# GeniusTop.net
KiCad netlist of a schematic drawn in EAGLE
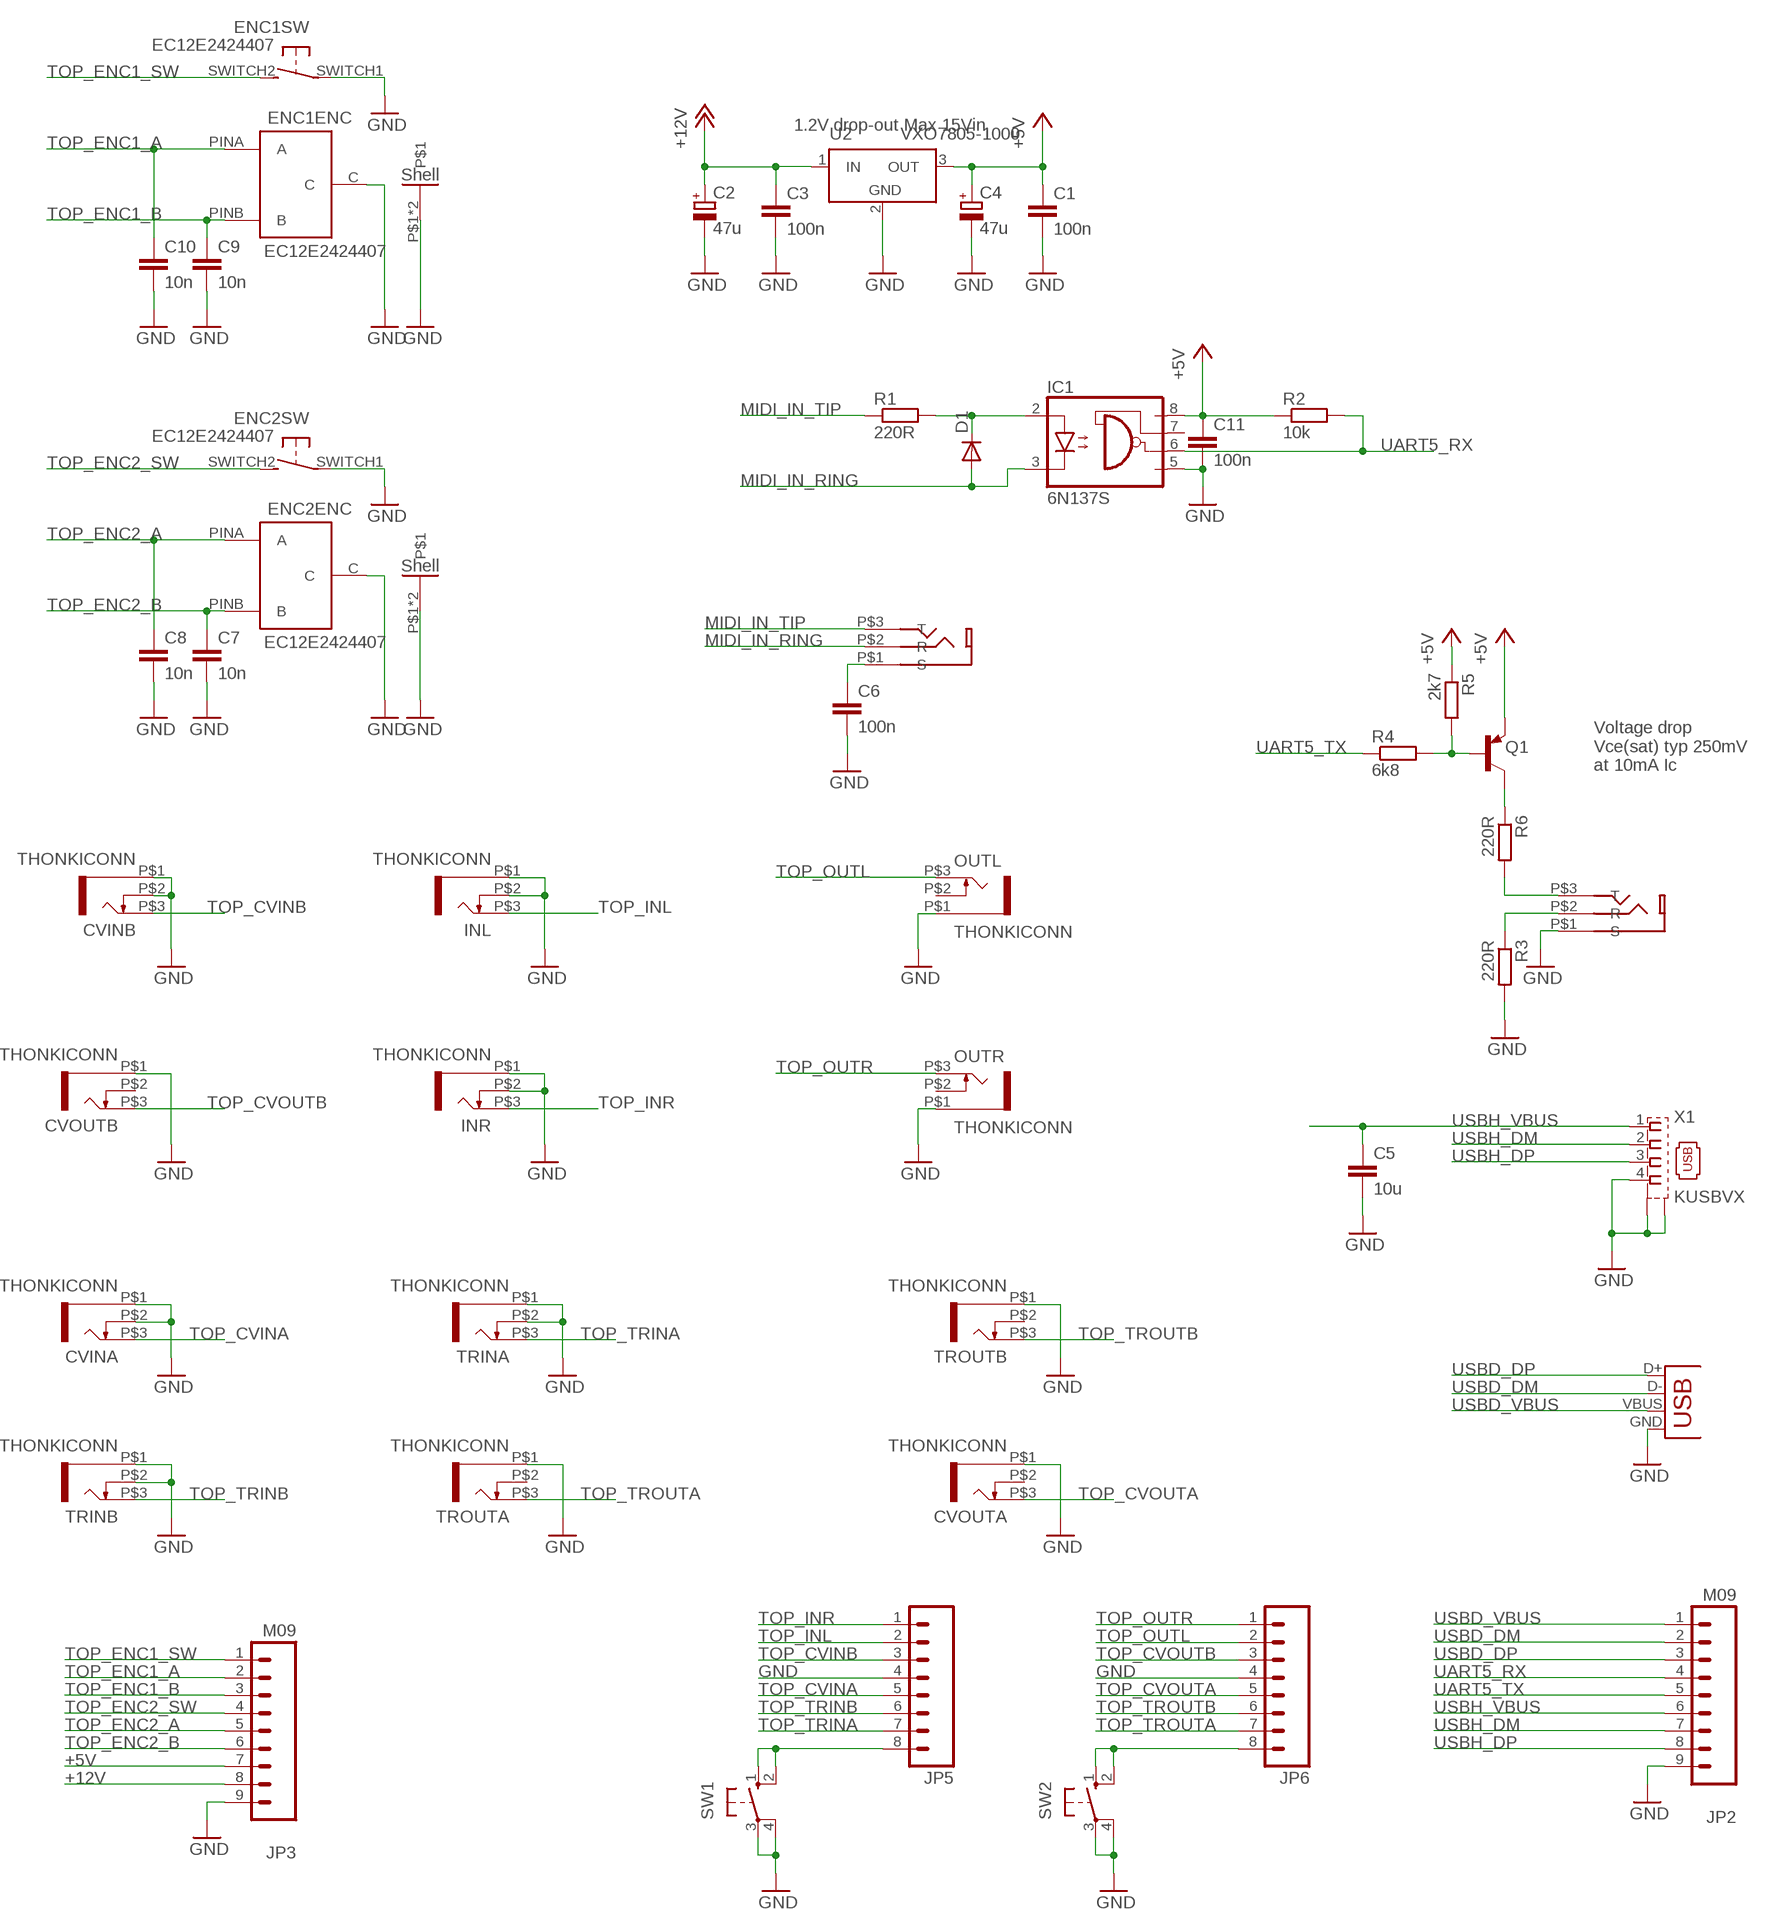
[diagram p0: schematic, sheet 1]

(export (version "E")
  (design (tool "Eeschema 10.0.6"))
  (components
    (comp (ref "C1")
      (value "100n")
      (footprint "eagle-import:C0603")
      (libsource (lib "eagle-import") (part "C-EUC0603"))
    )
    (comp (ref "C2")
      (value "47u")
      (footprint "eagle-import:CPOL-5")
      (libsource (lib "eagle-import") (part "CPOL-EU153CLV-0505"))
    )
    (comp (ref "C3")
      (value "100n")
      (footprint "eagle-import:C0603")
      (libsource (lib "eagle-import") (part "C-EUC0603"))
    )
    (comp (ref "C4")
      (value "47u")
      (footprint "eagle-import:CPOL-5")
      (libsource (lib "eagle-import") (part "CPOL-EU153CLV-0505"))
    )
    (comp (ref "C5")
      (value "10u")
      (footprint "eagle-import:C1206")
      (libsource (lib "eagle-import") (part "C-EUC1206"))
    )
    (comp (ref "C6")
      (value "100n")
      (footprint "eagle-import:C0603")
      (libsource (lib "eagle-import") (part "C-EUC0603"))
    )
    (comp (ref "C7")
      (value "10n")
      (footprint "eagle-import:C0603")
      (libsource (lib "eagle-import") (part "C-EUC0603"))
    )
    (comp (ref "C8")
      (value "10n")
      (footprint "eagle-import:C0603")
      (libsource (lib "eagle-import") (part "C-EUC0603"))
    )
    (comp (ref "C9")
      (value "10n")
      (footprint "eagle-import:C0603")
      (libsource (lib "eagle-import") (part "C-EUC0603"))
    )
    (comp (ref "C10")
      (value "10n")
      (footprint "eagle-import:C0603")
      (libsource (lib "eagle-import") (part "C-EUC0603"))
    )
    (comp (ref "C11")
      (value "100n")
      (footprint "eagle-import:C0603")
      (libsource (lib "eagle-import") (part "C-EUC0603"))
    )
    (comp (ref "CVINA")
      (value "THONKICONN")
      (footprint "eagle-import:THONKICONN")
      (libsource (lib "eagle-import") (part "THONKICONN"))
    )
    (comp (ref "CVINB")
      (value "THONKICONN")
      (footprint "eagle-import:THONKICONN")
      (libsource (lib "eagle-import") (part "THONKICONN"))
    )
    (comp (ref "CVOUTA")
      (value "THONKICONN")
      (footprint "eagle-import:THONKICONN")
      (libsource (lib "eagle-import") (part "THONKICONN"))
    )
    (comp (ref "CVOUTB")
      (value "THONKICONN")
      (footprint "eagle-import:THONKICONN")
      (libsource (lib "eagle-import") (part "THONKICONN"))
    )
    (comp (ref "D1")
      (value "DIODESOD-123")
      (footprint "eagle-import:SOD-123")
      (libsource (lib "eagle-import") (part "DIODESOD-123"))
    )
    (comp (ref "ENC1")
      (value "EC12E2424407")
      (footprint "eagle-import:EC12E2424407")
      (libsource (lib "eagle-import") (part "EC12E2424407"))
    )
    (comp (ref "ENC2")
      (value "EC12E2424407")
      (footprint "eagle-import:EC12E2424407")
      (libsource (lib "eagle-import") (part "EC12E2424407"))
    )
    (comp (ref "IC1")
      (value "6N137S")
      (footprint "eagle-import:DIL8-SMD")
      (libsource (lib "eagle-import") (part "6N137S"))
    )
    (comp (ref "INL")
      (value "THONKICONN")
      (footprint "eagle-import:THONKICONN")
      (libsource (lib "eagle-import") (part "THONKICONN"))
    )
    (comp (ref "INR")
      (value "THONKICONN")
      (footprint "eagle-import:THONKICONN")
      (libsource (lib "eagle-import") (part "THONKICONN"))
    )
    (comp (ref "JP2")
      (value "M09")
      (footprint "eagle-import:1X09")
      (libsource (lib "eagle-import") (part "M09"))
    )
    (comp (ref "JP3")
      (value "M09")
      (footprint "eagle-import:1X09")
      (libsource (lib "eagle-import") (part "M09"))
    )
    (comp (ref "JP5")
      (value "M081X08")
      (footprint "eagle-import:1X08")
      (libsource (lib "eagle-import") (part "M081X08"))
    )
    (comp (ref "JP6")
      (value "M081X08")
      (footprint "eagle-import:1X08")
      (libsource (lib "eagle-import") (part "M081X08"))
    )
    (comp (ref "MIDI_IN")
      (value "THONKICONN_STEREO")
      (footprint "eagle-import:THONKICONN_STEREO")
      (libsource (lib "eagle-import") (part "THONKICONN_STEREO"))
    )
    (comp (ref "MIDI_OUT")
      (value "THONKICONN_STEREO")
      (footprint "eagle-import:THONKICONN_STEREO")
      (libsource (lib "eagle-import") (part "THONKICONN_STEREO"))
    )
    (comp (ref "OUTL")
      (value "THONKICONN")
      (footprint "eagle-import:THONKICONN")
      (libsource (lib "eagle-import") (part "THONKICONN"))
    )
    (comp (ref "OUTR")
      (value "THONKICONN")
      (footprint "eagle-import:THONKICONN")
      (libsource (lib "eagle-import") (part "THONKICONN"))
    )
    (comp (ref "Q1")
      (value "MMBT3906LT1-PNP-SOT23-BEC")
      (footprint "eagle-import:SOT23-BEC")
      (libsource (lib "eagle-import") (part "-PNP-SOT23-BECMMBT3906LT1"))
    )
    (comp (ref "R1")
      (value "220R")
      (footprint "eagle-import:0603")
      (libsource (lib "eagle-import") (part "R-EU_R0603"))
    )
    (comp (ref "R2")
      (value "10k")
      (footprint "eagle-import:0603")
      (libsource (lib "eagle-import") (part "R-EU_R0603"))
    )
    (comp (ref "R3")
      (value "220R")
      (footprint "eagle-import:0603")
      (libsource (lib "eagle-import") (part "R-EU_R0603"))
    )
    (comp (ref "R4")
      (value "6k8")
      (footprint "eagle-import:0603")
      (libsource (lib "eagle-import") (part "R-EU_R0603"))
    )
    (comp (ref "R5")
      (value "2k7")
      (footprint "eagle-import:0603")
      (libsource (lib "eagle-import") (part "R-EU_R0603"))
    )
    (comp (ref "R6")
      (value "220R")
      (footprint "eagle-import:0603")
      (libsource (lib "eagle-import") (part "R-EU_R0603"))
    )
    (comp (ref "SW1")
      (value "10-XX")
      (footprint "eagle-import:B3F-10XX")
      (fields (field (name "MPN") "B3F-1000"))
      (libsource (lib "eagle-import") (part "10-XX"))
    )
    (comp (ref "SW2")
      (value "10-XX")
      (footprint "eagle-import:B3F-10XX")
      (fields (field (name "MPN") "B3F-1000"))
      (libsource (lib "eagle-import") (part "10-XX"))
    )
    (comp (ref "TRINA")
      (value "THONKICONN")
      (footprint "eagle-import:THONKICONN")
      (libsource (lib "eagle-import") (part "THONKICONN"))
    )
    (comp (ref "TRINB")
      (value "THONKICONN")
      (footprint "eagle-import:THONKICONN")
      (libsource (lib "eagle-import") (part "THONKICONN"))
    )
    (comp (ref "TROUTA")
      (value "THONKICONN")
      (footprint "eagle-import:THONKICONN")
      (libsource (lib "eagle-import") (part "THONKICONN"))
    )
    (comp (ref "TROUTB")
      (value "THONKICONN")
      (footprint "eagle-import:THONKICONN")
      (libsource (lib "eagle-import") (part "THONKICONN"))
    )
    (comp (ref "U2")
      (value "VXO7805-1000")
      (footprint "eagle-import:TSR-1-2450")
      (libsource (lib "eagle-import") (part "TSR-1-2450"))
    )
    (comp (ref "X1")
      (value "KUSBVX")
      (footprint "eagle-import:KUSBVX")
      (libsource (lib "eagle-import") (part "KUSBVX"))
    )
    (comp (ref "X2")
      (value "USBPTH-VERTICAL")
      (footprint "eagle-import:USB-B-PTH-VERTICAL")
      (libsource (lib "eagle-import") (part "USBPTH-VERTICAL"))
    )
  )
  (nets
    (net (code "1") (name "+5V") (class "Default")
      (node (ref "C1") (pin "1") (pinfunction "1_1") (pintype "passive"))
      (node (ref "C11") (pin "1") (pinfunction "1_1") (pintype "passive"))
      (node (ref "C4") (pin "+") (pinfunction "+_+") (pintype "passive"))
      (node (ref "IC1") (pin "8") (pinfunction "VCC_8") (pintype "passive"))
      (node (ref "JP3") (pin "7") (pinfunction "7_7") (pintype "passive"))
      (node (ref "Q1") (pin "E") (pinfunction "E_E") (pintype "passive"))
      (node (ref "R2") (pin "1") (pinfunction "1_1") (pintype "passive"))
      (node (ref "R5") (pin "1") (pinfunction "1_1") (pintype "passive"))
      (node (ref "U2") (pin "3") (pinfunction "OUT_3") (pintype "output"))
    )
    (net (code "2") (name "+12V") (class "Default")
      (node (ref "C2") (pin "+") (pinfunction "+_+") (pintype "passive"))
      (node (ref "C3") (pin "1") (pinfunction "1_1") (pintype "passive"))
      (node (ref "JP3") (pin "8") (pinfunction "8_8") (pintype "passive"))
      (node (ref "U2") (pin "1") (pinfunction "IN_1") (pintype "input"))
    )
    (net (code "3") (name "/MIDI_IN_RING") (class "Default")
      (node (ref "D1") (pin "A") (pinfunction "A_A") (pintype "passive"))
      (node (ref "IC1") (pin "3") (pinfunction "C_3") (pintype "passive"))
      (node (ref "MIDI_IN") (pin "P$2") (pinfunction "R_P$2") (pintype "bidirectional"))
    )
    (net (code "4") (name "/MIDI_IN_TIP") (class "Default")
      (node (ref "MIDI_IN") (pin "P$3") (pinfunction "T_P$3") (pintype "bidirectional"))
      (node (ref "R1") (pin "1") (pinfunction "1_1") (pintype "passive"))
    )
    (net (code "5") (name "/TOP_CVINA") (class "Default")
      (node (ref "CVINA") (pin "P$3") (pinfunction "3_P$3") (pintype "passive"))
      (node (ref "JP5") (pin "5") (pinfunction "5_5") (pintype "passive"))
    )
    (net (code "6") (name "/TOP_CVINB") (class "Default")
      (node (ref "CVINB") (pin "P$3") (pinfunction "3_P$3") (pintype "passive"))
      (node (ref "JP5") (pin "3") (pinfunction "3_3") (pintype "passive"))
    )
    (net (code "7") (name "/TOP_CVOUTA") (class "Default")
      (node (ref "CVOUTA") (pin "P$3") (pinfunction "3_P$3") (pintype "passive"))
      (node (ref "JP6") (pin "5") (pinfunction "5_5") (pintype "passive"))
    )
    (net (code "8") (name "/TOP_CVOUTB") (class "Default")
      (node (ref "CVOUTB") (pin "P$3") (pinfunction "3_P$3") (pintype "passive"))
      (node (ref "JP6") (pin "3") (pinfunction "3_3") (pintype "passive"))
    )
    (net (code "9") (name "/TOP_ENC1_A") (class "Default")
      (node (ref "C10") (pin "1") (pinfunction "1_1") (pintype "passive"))
      (node (ref "ENC1") (pin "PINA") (pinfunction "A_PINA") (pintype "bidirectional"))
      (node (ref "JP3") (pin "2") (pinfunction "2_2") (pintype "passive"))
    )
    (net (code "10") (name "/TOP_ENC1_B") (class "Default")
      (node (ref "C9") (pin "1") (pinfunction "1_1") (pintype "passive"))
      (node (ref "ENC1") (pin "PINB") (pinfunction "B_PINB") (pintype "bidirectional"))
      (node (ref "JP3") (pin "3") (pinfunction "3_3") (pintype "passive"))
    )
    (net (code "11") (name "/TOP_ENC1_SW") (class "Default")
      (node (ref "ENC1") (pin "SWITCH2") (pinfunction "S_SWITCH2") (pintype "passive"))
      (node (ref "JP3") (pin "1") (pinfunction "1_1") (pintype "passive"))
    )
    (net (code "12") (name "/TOP_ENC2_A") (class "Default")
      (node (ref "C8") (pin "1") (pinfunction "1_1") (pintype "passive"))
      (node (ref "ENC2") (pin "PINA") (pinfunction "A_PINA") (pintype "bidirectional"))
      (node (ref "JP3") (pin "5") (pinfunction "5_5") (pintype "passive"))
    )
    (net (code "13") (name "/TOP_ENC2_B") (class "Default")
      (node (ref "C7") (pin "1") (pinfunction "1_1") (pintype "passive"))
      (node (ref "ENC2") (pin "PINB") (pinfunction "B_PINB") (pintype "bidirectional"))
      (node (ref "JP3") (pin "6") (pinfunction "6_6") (pintype "passive"))
    )
    (net (code "14") (name "/TOP_ENC2_SW") (class "Default")
      (node (ref "ENC2") (pin "SWITCH2") (pinfunction "S_SWITCH2") (pintype "passive"))
      (node (ref "JP3") (pin "4") (pinfunction "4_4") (pintype "passive"))
    )
    (net (code "15") (name "/TOP_INL") (class "Default")
      (node (ref "INL") (pin "P$3") (pinfunction "3_P$3") (pintype "passive"))
      (node (ref "JP5") (pin "2") (pinfunction "2_2") (pintype "passive"))
    )
    (net (code "16") (name "/TOP_INR") (class "Default")
      (node (ref "INR") (pin "P$3") (pinfunction "3_P$3") (pintype "passive"))
      (node (ref "JP5") (pin "1") (pinfunction "1_1") (pintype "passive"))
    )
    (net (code "17") (name "/TOP_OUTL") (class "Default")
      (node (ref "JP6") (pin "2") (pinfunction "2_2") (pintype "passive"))
      (node (ref "OUTL") (pin "P$3") (pinfunction "3_P$3") (pintype "passive"))
    )
    (net (code "18") (name "/TOP_OUTR") (class "Default")
      (node (ref "JP6") (pin "1") (pinfunction "1_1") (pintype "passive"))
      (node (ref "OUTR") (pin "P$3") (pinfunction "3_P$3") (pintype "passive"))
    )
    (net (code "19") (name "/TOP_TRINA") (class "Default")
      (node (ref "JP5") (pin "7") (pinfunction "7_7") (pintype "passive"))
      (node (ref "TRINA") (pin "P$3") (pinfunction "3_P$3") (pintype "passive"))
    )
    (net (code "20") (name "/TOP_TRINB") (class "Default")
      (node (ref "JP5") (pin "6") (pinfunction "6_6") (pintype "passive"))
      (node (ref "TRINB") (pin "P$3") (pinfunction "3_P$3") (pintype "passive"))
    )
    (net (code "21") (name "/TOP_TROUTA") (class "Default")
      (node (ref "JP6") (pin "7") (pinfunction "7_7") (pintype "passive"))
      (node (ref "TROUTA") (pin "P$3") (pinfunction "3_P$3") (pintype "passive"))
    )
    (net (code "22") (name "/TOP_TROUTB") (class "Default")
      (node (ref "JP6") (pin "6") (pinfunction "6_6") (pintype "passive"))
      (node (ref "TROUTB") (pin "P$3") (pinfunction "3_P$3") (pintype "passive"))
    )
    (net (code "23") (name "/UART5_RX") (class "Default")
      (node (ref "IC1") (pin "6") (pinfunction "VO_6") (pintype "passive"))
      (node (ref "JP2") (pin "4") (pinfunction "4_4") (pintype "passive"))
      (node (ref "R2") (pin "2") (pinfunction "2_2") (pintype "passive"))
    )
    (net (code "24") (name "/UART5_TX") (class "Default")
      (node (ref "JP2") (pin "5") (pinfunction "5_5") (pintype "passive"))
      (node (ref "R4") (pin "1") (pinfunction "1_1") (pintype "passive"))
    )
    (net (code "25") (name "/USBD_DM") (class "Default")
      (node (ref "JP2") (pin "2") (pinfunction "2_2") (pintype "passive"))
      (node (ref "X2") (pin "D-") (pinfunction "D-_D-") (pintype "bidirectional"))
    )
    (net (code "26") (name "/USBD_DP") (class "Default")
      (node (ref "JP2") (pin "3") (pinfunction "3_3") (pintype "passive"))
      (node (ref "X2") (pin "D+") (pinfunction "D+_D+") (pintype "bidirectional"))
    )
    (net (code "27") (name "/USBD_VBUS") (class "Default")
      (node (ref "JP2") (pin "1") (pinfunction "1_1") (pintype "passive"))
      (node (ref "X2") (pin "VBUS") (pinfunction "VBUS_VBUS") (pintype "bidirectional"))
    )
    (net (code "28") (name "/USBH_DM") (class "Default")
      (node (ref "JP2") (pin "7") (pinfunction "7_7") (pintype "passive"))
      (node (ref "X1") (pin "2") (pinfunction "2_2") (pintype "passive"))
    )
    (net (code "29") (name "/USBH_DP") (class "Default")
      (node (ref "JP2") (pin "8") (pinfunction "8_8") (pintype "passive"))
      (node (ref "X1") (pin "3") (pinfunction "3_3") (pintype "passive"))
    )
    (net (code "30") (name "/USBH_VBUS") (class "Default")
      (node (ref "C5") (pin "1") (pinfunction "1_1") (pintype "passive"))
      (node (ref "JP2") (pin "6") (pinfunction "6_6") (pintype "passive"))
      (node (ref "X1") (pin "1") (pinfunction "1_1") (pintype "passive"))
    )
    (net (code "31") (name "GND") (class "Default")
      (node (ref "C1") (pin "2") (pinfunction "2_2") (pintype "passive"))
      (node (ref "C10") (pin "2") (pinfunction "2_2") (pintype "passive"))
      (node (ref "C11") (pin "2") (pinfunction "2_2") (pintype "passive"))
      (node (ref "C2") (pin "-") (pinfunction "-_-") (pintype "passive"))
      (node (ref "C3") (pin "2") (pinfunction "2_2") (pintype "passive"))
      (node (ref "C4") (pin "-") (pinfunction "-_-") (pintype "passive"))
      (node (ref "C5") (pin "2") (pinfunction "2_2") (pintype "passive"))
      (node (ref "C6") (pin "2") (pinfunction "2_2") (pintype "passive"))
      (node (ref "C7") (pin "2") (pinfunction "2_2") (pintype "passive"))
      (node (ref "C8") (pin "2") (pinfunction "2_2") (pintype "passive"))
      (node (ref "C9") (pin "2") (pinfunction "2_2") (pintype "passive"))
      (node (ref "CVINA") (pin "P$1") (pinfunction "5_P$1") (pintype "passive"))
      (node (ref "CVINA") (pin "P$2") (pinfunction "4_P$2") (pintype "passive"))
      (node (ref "CVINB") (pin "P$1") (pinfunction "5_P$1") (pintype "passive"))
      (node (ref "CVINB") (pin "P$2") (pinfunction "4_P$2") (pintype "passive"))
      (node (ref "CVOUTA") (pin "P$1") (pinfunction "5_P$1") (pintype "passive"))
      (node (ref "CVOUTB") (pin "P$1") (pinfunction "5_P$1") (pintype "passive"))
      (node (ref "ENC1") (pin "C") (pinfunction "C_C") (pintype "bidirectional"))
      (node (ref "ENC1") (pin "P$1") (pinfunction "P$1_P$1") (pintype "bidirectional"))
      (node (ref "ENC1") (pin "P$2") (pinfunction "P$1_P$2") (pintype "bidirectional"))
      (node (ref "ENC1") (pin "SWITCH1") (pinfunction "P_SWITCH1") (pintype "passive"))
      (node (ref "ENC2") (pin "C") (pinfunction "C_C") (pintype "bidirectional"))
      (node (ref "ENC2") (pin "P$1") (pinfunction "P$1_P$1") (pintype "bidirectional"))
      (node (ref "ENC2") (pin "P$2") (pinfunction "P$1_P$2") (pintype "bidirectional"))
      (node (ref "ENC2") (pin "SWITCH1") (pinfunction "P_SWITCH1") (pintype "passive"))
      (node (ref "IC1") (pin "5") (pinfunction "GND_5") (pintype "passive"))
      (node (ref "INL") (pin "P$1") (pinfunction "5_P$1") (pintype "passive"))
      (node (ref "INL") (pin "P$2") (pinfunction "4_P$2") (pintype "passive"))
      (node (ref "INR") (pin "P$1") (pinfunction "5_P$1") (pintype "passive"))
      (node (ref "INR") (pin "P$2") (pinfunction "4_P$2") (pintype "passive"))
      (node (ref "JP2") (pin "9") (pinfunction "9_9") (pintype "passive"))
      (node (ref "JP3") (pin "9") (pinfunction "9_9") (pintype "passive"))
      (node (ref "JP5") (pin "4") (pinfunction "4_4") (pintype "passive"))
      (node (ref "JP6") (pin "4") (pinfunction "4_4") (pintype "passive"))
      (node (ref "MIDI_OUT") (pin "P$1") (pinfunction "S_P$1") (pintype "bidirectional"))
      (node (ref "OUTL") (pin "P$1") (pinfunction "5_P$1") (pintype "passive"))
      (node (ref "OUTR") (pin "P$1") (pinfunction "5_P$1") (pintype "passive"))
      (node (ref "R3") (pin "2") (pinfunction "2_2") (pintype "passive"))
      (node (ref "SW1") (pin "3") (pinfunction "P_3") (pintype "passive"))
      (node (ref "SW1") (pin "4") (pinfunction "P1_4") (pintype "passive"))
      (node (ref "SW2") (pin "3") (pinfunction "P_3") (pintype "passive"))
      (node (ref "SW2") (pin "4") (pinfunction "P1_4") (pintype "passive"))
      (node (ref "TRINA") (pin "P$1") (pinfunction "5_P$1") (pintype "passive"))
      (node (ref "TRINA") (pin "P$2") (pinfunction "4_P$2") (pintype "passive"))
      (node (ref "TRINB") (pin "P$1") (pinfunction "5_P$1") (pintype "passive"))
      (node (ref "TRINB") (pin "P$2") (pinfunction "4_P$2") (pintype "passive"))
      (node (ref "TROUTA") (pin "P$1") (pinfunction "5_P$1") (pintype "passive"))
      (node (ref "TROUTB") (pin "P$1") (pinfunction "5_P$1") (pintype "passive"))
      (node (ref "U2") (pin "2") (pinfunction "GND_2") (pintype "power_in"))
      (node (ref "X1") (pin "4") (pinfunction "4_4") (pintype "passive"))
      (node (ref "X1") (pin "M1") (pinfunction "S1_M1") (pintype "passive"))
      (node (ref "X1") (pin "M2") (pinfunction "S2_M2") (pintype "passive"))
      (node (ref "X2") (pin "GND") (pinfunction "GND_GND") (pintype "bidirectional"))
    )
    (net (code "32") (name "Net-(IC1-A)") (class "Default")
      (node (ref "D1") (pin "C") (pinfunction "C_C") (pintype "passive"))
      (node (ref "IC1") (pin "2") (pinfunction "A_2") (pintype "passive"))
      (node (ref "R1") (pin "2") (pinfunction "2_2") (pintype "passive"))
    )
    (net (code "33") (name "Net-(MIDI_IN-S)") (class "Default")
      (node (ref "C6") (pin "1") (pinfunction "1_1") (pintype "passive"))
      (node (ref "MIDI_IN") (pin "P$1") (pinfunction "S_P$1") (pintype "bidirectional"))
    )
    (net (code "34") (name "Net-(MIDI_OUT-R)") (class "Default")
      (node (ref "MIDI_OUT") (pin "P$2") (pinfunction "R_P$2") (pintype "bidirectional"))
      (node (ref "R3") (pin "1") (pinfunction "1_1") (pintype "passive"))
    )
    (net (code "35") (name "Net-(MIDI_OUT-T)") (class "Default")
      (node (ref "MIDI_OUT") (pin "P$3") (pinfunction "T_P$3") (pintype "bidirectional"))
      (node (ref "R6") (pin "2") (pinfunction "2_2") (pintype "passive"))
    )
    (net (code "36") (name "Net-(Q1-PadB)") (class "Default")
      (node (ref "Q1") (pin "B") (pinfunction "B_B") (pintype "passive"))
      (node (ref "R4") (pin "2") (pinfunction "2_2") (pintype "passive"))
      (node (ref "R5") (pin "2") (pinfunction "2_2") (pintype "passive"))
    )
    (net (code "37") (name "Net-(Q1-PadC)") (class "Default")
      (node (ref "Q1") (pin "C") (pinfunction "C_C") (pintype "passive"))
      (node (ref "R6") (pin "1") (pinfunction "1_1") (pintype "passive"))
    )
    (net (code "38") (name "Net-(SW1-S)") (class "Default")
      (node (ref "JP5") (pin "8") (pinfunction "8_8") (pintype "passive"))
      (node (ref "SW1") (pin "1") (pinfunction "S_1") (pintype "passive"))
      (node (ref "SW1") (pin "2") (pinfunction "S1_2") (pintype "passive"))
    )
    (net (code "39") (name "Net-(SW2-S)") (class "Default")
      (node (ref "JP6") (pin "8") (pinfunction "8_8") (pintype "passive"))
      (node (ref "SW2") (pin "1") (pinfunction "S_1") (pintype "passive"))
      (node (ref "SW2") (pin "2") (pinfunction "S1_2") (pintype "passive"))
    )
    (net (code "40") (name "unconnected-(CVOUTA-4-PadP$2)") (class "Default")
      (node (ref "CVOUTA") (pin "P$2") (pinfunction "4_P$2") (pintype "passive"))
    )
    (net (code "41") (name "unconnected-(CVOUTB-4-PadP$2)") (class "Default")
      (node (ref "CVOUTB") (pin "P$2") (pinfunction "4_P$2") (pintype "passive"))
    )
    (net (code "42") (name "unconnected-(IC1-VE-Pad7)") (class "Default")
      (node (ref "IC1") (pin "7") (pinfunction "VE_7") (pintype "passive"))
    )
    (net (code "43") (name "unconnected-(OUTL-4-PadP$2)") (class "Default")
      (node (ref "OUTL") (pin "P$2") (pinfunction "4_P$2") (pintype "passive"))
    )
    (net (code "44") (name "unconnected-(OUTR-4-PadP$2)") (class "Default")
      (node (ref "OUTR") (pin "P$2") (pinfunction "4_P$2") (pintype "passive"))
    )
    (net (code "45") (name "unconnected-(TROUTA-4-PadP$2)") (class "Default")
      (node (ref "TROUTA") (pin "P$2") (pinfunction "4_P$2") (pintype "passive"))
    )
    (net (code "46") (name "unconnected-(TROUTB-4-PadP$2)") (class "Default")
      (node (ref "TROUTB") (pin "P$2") (pinfunction "4_P$2") (pintype "passive"))
    )
  )
)
